# 4_STM32KIT_MCU.net
KiCad netlist of a schematic drawn in Altium Designer
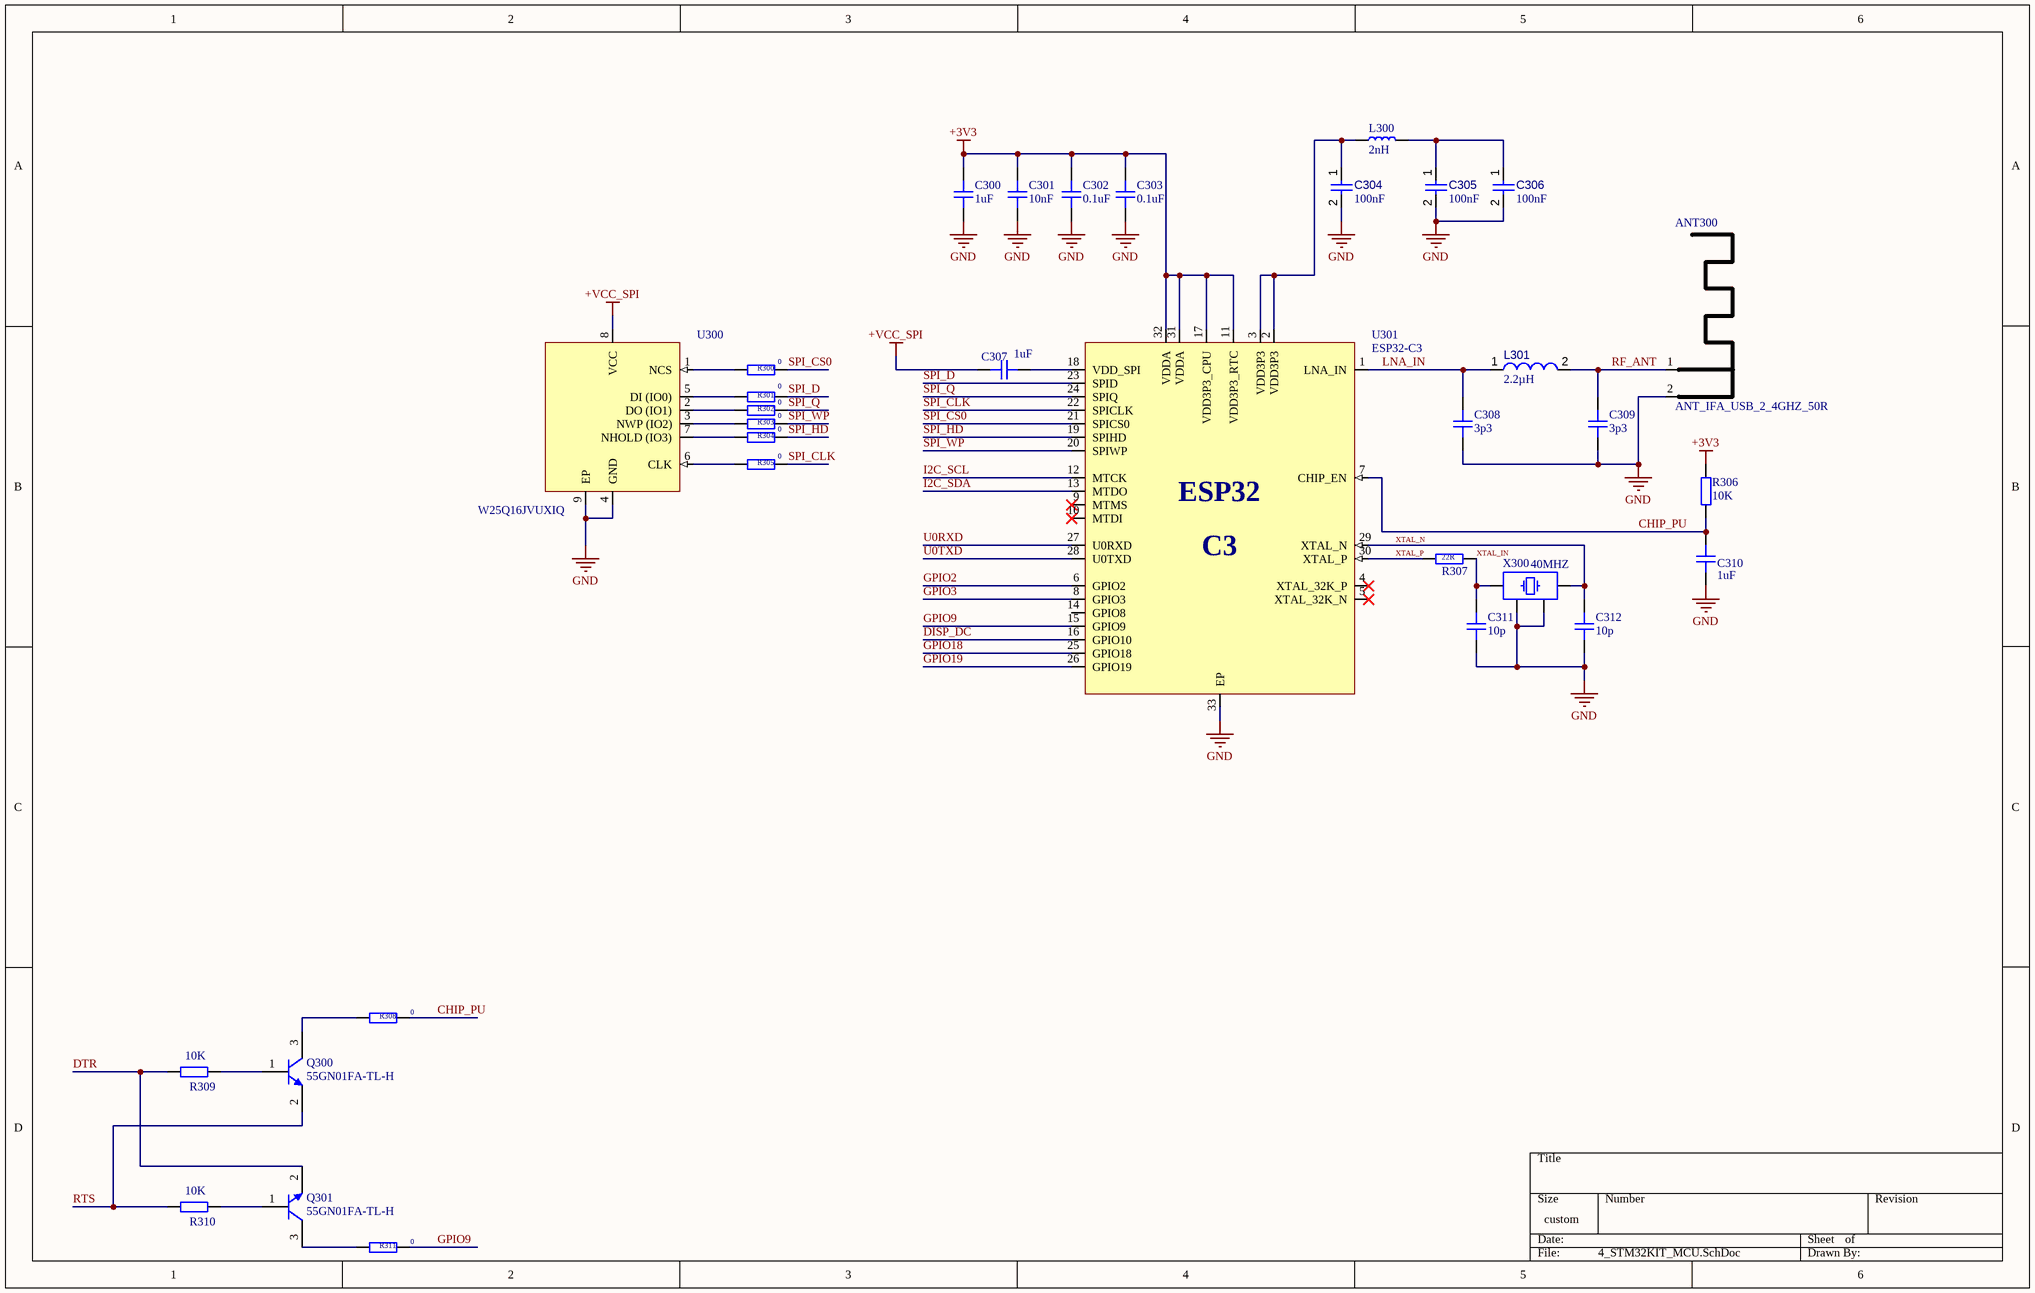
[diagram p0: 4_STM32KIT_MCU.SchDoc]

(export (version "E")
  (design (tool "Eeschema 10.0.6"))
  (components
    (comp (ref "ANT300")
      (value "ANT_IFA_USB_2_4GHZ_50R")
      (footprint "ANT_IFA_USB_2_4GHZ_50R")
      (description "Inverted F 2.4GHz ISM PCB Antenna 50 Ohm")
      (fields (field (name "SOURCE") "Schematic-Lib-PhilsLab.SchLib"))
      (libsource (lib "Industrial University of Ho Chi Minh City") (part "ANT_IFA_USB_2_4GHZ_50R"))
    )
    (comp (ref "C300")
      (value "1uF")
      (footprint "CAP_0402")
      (description "Capacitor SMD 0402 50V")
      (fields
        (field (name "MANUFACTURER") "Samsung")
        (field (name "MANUFACTURER PART NUMBER") "CL05B104KO5NNNC")
      )
      (libsource (lib "Schematic-Lib-PhilsLab") (part "CAP_0402_50V"))
    )
    (comp (ref "C301")
      (value "10nF")
      (footprint "CAP_0402")
      (description "Capacitor SMD 0402 50V")
      (fields
        (field (name "MANUFACTURER") "Samsung")
        (field (name "MANUFACTURER PART NUMBER") "CL05B104KO5NNNC")
      )
      (libsource (lib "Schematic-Lib-PhilsLab") (part "CAP_0402_50V"))
    )
    (comp (ref "C302")
      (value "0.1uF")
      (footprint "CAP_0402")
      (description "Capacitor SMD 0402 50V")
      (fields
        (field (name "MANUFACTURER") "Samsung")
        (field (name "MANUFACTURER PART NUMBER") "CL05B104KO5NNNC")
      )
      (libsource (lib "Schematic-Lib-PhilsLab") (part "CAP_0402_50V"))
    )
    (comp (ref "C303")
      (value "0.1uF")
      (footprint "CAP_0402")
      (description "Capacitor SMD 0402 50V")
      (fields
        (field (name "MANUFACTURER") "Samsung")
        (field (name "MANUFACTURER PART NUMBER") "CL05B104KO5NNNC")
      )
      (libsource (lib "Schematic-Lib-PhilsLab") (part "CAP_0402_50V"))
    )
    (comp (ref "C304")
      (value "100nF")
      (footprint "CAPC1005X56X25LL10T15")
      (description "Chip Capacitor, 0.1 uF, +/- 5%, 16 V, 0402 (1005 Metric)")
      (fields (field (name "TOLERANCE") "5%") (field (name "Comment") "Capacitor 0.1 uF +/- 5% 16 V 0402"))
      (libsource (lib "Industrial University of Ho Chi Minh City") (part "CAP-NP-2"))
    )
    (comp (ref "C305")
      (value "100nF")
      (footprint "CAPC1005X56X25LL10T15")
      (description "Chip Capacitor, 0.1 uF, +/- 5%, 16 V, 0402 (1005 Metric)")
      (fields (field (name "TOLERANCE") "5%") (field (name "Comment") "Capacitor 0.1 uF +/- 5% 16 V 0402"))
      (libsource (lib "Industrial University of Ho Chi Minh City") (part "CAP-NP-2"))
    )
    (comp (ref "C306")
      (value "100nF")
      (footprint "CAPC1005X56X25LL10T15")
      (description "Chip Capacitor, 0.1 uF, +/- 5%, 16 V, 0402 (1005 Metric)")
      (fields (field (name "TOLERANCE") "5%") (field (name "Comment") "10u"))
      (libsource (lib "Industrial University of Ho Chi Minh City") (part "CAP-NP-2"))
    )
    (comp (ref "C307")
      (value "1uF")
      (footprint "CAP_0402")
      (description "Capacitor SMD 0402")
      (fields (field (name "SOURCE") "Schematic-Lib-PhilsLab.SchLib"))
      (libsource (lib "Industrial University of Ho Chi Minh City") (part "CAP_EL_NP_5MM"))
    )
    (comp (ref "C308")
      (value "3p3")
      (footprint "CAP_0402")
      (description "Capacitor SMD 0402")
      (libsource (lib "Schematic-Lib-PhilsLab") (part "CAP_0402"))
    )
    (comp (ref "C309")
      (value "3p3")
      (footprint "CAP_0402")
      (description "Capacitor SMD 0402")
      (libsource (lib "Schematic-Lib-PhilsLab") (part "CAP_0402"))
    )
    (comp (ref "C310")
      (value "1uF")
      (footprint "CAP_0402")
      (description "Capacitor SMD 0402")
      (fields (field (name "SOURCE") "Schematic-Lib-PhilsLab.SchLib"))
      (libsource (lib "Industrial University of Ho Chi Minh City") (part "CAP_EL_NP_5MM"))
    )
    (comp (ref "C311")
      (value "10p")
      (footprint "CAP_0402")
      (description "Capacitor SMD 0402")
      (libsource (lib "Schematic-Lib-PhilsLab") (part "CAP_0402"))
    )
    (comp (ref "C312")
      (value "10p")
      (footprint "CAP_0402")
      (description "Capacitor SMD 0402")
      (libsource (lib "Schematic-Lib-PhilsLab") (part "CAP_0402"))
    )
    (comp (ref "L300")
      (value "2nH")
      (footprint "IND_0402")
      (description "Inductor SMD 0402")
      (libsource (lib "Schematic-Lib-PhilsLab") (part "IND_0402"))
    )
    (comp (ref "L301")
      (value "2.2µH")
      (footprint "IND1005X55X20VL5T10")
      (description "Chip Inductor, 2.2 nH, +/- 0.3 nH, 400 mA, -40 to 85 degC, 0402 (1005 Metric), RoHS, Tape and Reel")
      (fields (field (name "MANUFACTURER") "Panasonic") (field (name "TOLERANCE") "5%"))
      (libsource (lib "Industrial University of Ho Chi Minh City") (part "IND-2"))
    )
    (comp (ref "Q300")
      (value "55GN01FA-TL-H")
      (footprint "ONSC-SSFP-3_V")
      (description "RF Transistor, 10 V, 70 mA, fT=5.5 GHz, NPN Single, 3-Pin SSFP, Pb-Free, Tape and Reel")
      (fields (field (name "MANUFACTURER") "On Semiconductor"))
      (libsource (lib "Altium Content Vault") (part "ONSC-NPN-B1E2C3-3"))
    )
    (comp (ref "Q301")
      (value "55GN01FA-TL-H")
      (footprint "ONSC-SSFP-3_V")
      (description "RF Transistor, 10 V, 70 mA, fT=5.5 GHz, NPN Single, 3-Pin SSFP, Pb-Free, Tape and Reel")
      (fields (field (name "MANUFACTURER") "On Semiconductor"))
      (libsource (lib "Altium Content Vault") (part "ONSC-NPN-B1E2C3-3"))
    )
    (comp (ref "R300")
      (value "0")
      (footprint "RES_0402")
      (description "Resistor SMD 0402")
      (fields (field (name "SOURCE") "Schematic-Lib-PhilsLab.SchLib"))
      (libsource (lib "Industrial University of Ho Chi Minh City") (part "RES_5931"))
    )
    (comp (ref "R301")
      (value "0")
      (footprint "RES_0402")
      (description "Resistor SMD 0402")
      (fields (field (name "SOURCE") "Schematic-Lib-PhilsLab.SchLib"))
      (libsource (lib "Industrial University of Ho Chi Minh City") (part "RES_5931"))
    )
    (comp (ref "R302")
      (value "0")
      (footprint "RES_0402")
      (description "Resistor SMD 0402")
      (fields (field (name "SOURCE") "Schematic-Lib-PhilsLab.SchLib"))
      (libsource (lib "Industrial University of Ho Chi Minh City") (part "RES_5931"))
    )
    (comp (ref "R303")
      (value "0")
      (footprint "RES_0402")
      (description "Resistor SMD 0402")
      (fields (field (name "SOURCE") "Schematic-Lib-PhilsLab.SchLib"))
      (libsource (lib "Industrial University of Ho Chi Minh City") (part "RES_5931"))
    )
    (comp (ref "R304")
      (value "0")
      (footprint "RES_0402")
      (description "Resistor SMD 0402")
      (fields (field (name "SOURCE") "Schematic-Lib-PhilsLab.SchLib"))
      (libsource (lib "Industrial University of Ho Chi Minh City") (part "RES_5931"))
    )
    (comp (ref "R305")
      (value "0")
      (footprint "RES_0402")
      (description "Resistor SMD 0402")
      (fields (field (name "SOURCE") "Schematic-Lib-PhilsLab.SchLib"))
      (libsource (lib "Industrial University of Ho Chi Minh City") (part "RES_5931"))
    )
    (comp (ref "R306")
      (value "10K")
      (footprint "RES_0402")
      (description "Resistor SMD 0402")
      (fields (field (name "SOURCE") "Schematic-Lib-PhilsLab.SchLib"))
      (libsource (lib "Industrial University of Ho Chi Minh City") (part "RES_5931"))
    )
    (comp (ref "R307")
      (value "22R")
      (footprint "RES_0402")
      (description "Resistor SMD 0402")
      (fields (field (name "SOURCE") "Schematic-Lib-PhilsLab.SchLib"))
      (libsource (lib "Industrial University of Ho Chi Minh City") (part "RES_5931"))
    )
    (comp (ref "R308")
      (value "0")
      (footprint "RES_0402")
      (description "Resistor SMD 0402")
      (fields (field (name "SOURCE") "Schematic-Lib-PhilsLab.SchLib"))
      (libsource (lib "Industrial University of Ho Chi Minh City") (part "RES_5931"))
    )
    (comp (ref "R309")
      (value "10K")
      (footprint "RES_0402")
      (description "Resistor SMD 0402")
      (fields (field (name "SOURCE") "Schematic-Lib-PhilsLab.SchLib"))
      (libsource (lib "Industrial University of Ho Chi Minh City") (part "RES_5931"))
    )
    (comp (ref "R310")
      (value "10K")
      (footprint "RES_0402")
      (description "Resistor SMD 0402")
      (fields (field (name "SOURCE") "Schematic-Lib-PhilsLab.SchLib"))
      (libsource (lib "Industrial University of Ho Chi Minh City") (part "RES_5931"))
    )
    (comp (ref "R311")
      (value "0")
      (footprint "RES_0402")
      (description "Resistor SMD 0402")
      (fields (field (name "SOURCE") "Schematic-Lib-PhilsLab.SchLib"))
      (libsource (lib "Industrial University of Ho Chi Minh City") (part "RES_5931"))
    )
    (comp (ref "U300")
      (value "W25Q16JVUXIQ")
      (footprint "USON-8-2X3MM")
      (description "16M-BIT SERIAL FLASH MEMORY WITH DUAL/QUAD SPI USON-8")
      (fields (field (name "MANUFACTURER") "Winbond") (field (name "SOURCE") "Schematic-Lib-PhilsLab.SchLib"))
      (libsource (lib "Industrial University of Ho Chi Minh City") (part "W25Q16JVUXIQ"))
    )
    (comp (ref "U301")
      (value "ESP32-C3")
      (footprint "QFN32-5X5")
      (fields
        (field (name "MANUFACTURER") "Espressif")
        (field (name "SOURCE") "Schematic-Lib-PhilsLab.SchLib")
      )
      (libsource (lib "Industrial University of Ho Chi Minh City") (part "ESP32-C3"))
    )
    (comp (ref "X300")
      (value "40MHZ")
      (footprint "XTAL_2520")
      (description "Crystal SMD 2520")
      (libsource (lib "Schematic-Lib-PhilsLab") (part "XTAL_2520"))
    )
  )
  (nets
    (net (code "1") (name "+3V3") (class "Default")
      (node (ref "C300") (pin "2") (pinfunction "2_2") (pintype "passive"))
      (node (ref "C301") (pin "2") (pinfunction "2_2") (pintype "passive"))
      (node (ref "C302") (pin "2") (pinfunction "2_2") (pintype "passive"))
      (node (ref "C303") (pin "2") (pinfunction "2_2") (pintype "passive"))
      (node (ref "R306") (pin "2") (pinfunction "2_2") (pintype "passive"))
      (node (ref "U301") (pin "11") (pinfunction "VDD3P3_RTC_11") (pintype "power_in"))
      (node (ref "U301") (pin "17") (pinfunction "VDD3P3_CPU_17") (pintype "power_in"))
      (node (ref "U301") (pin "31") (pinfunction "VDDA_31") (pintype "power_in"))
      (node (ref "U301") (pin "32") (pinfunction "VDDA_32") (pintype "power_in"))
    )
    (net (code "2") (name "+VCC_SPI") (class "Default")
      (node (ref "C307") (pin "1") (pinfunction "1_1") (pintype "passive"))
      (node (ref "U300") (pin "8") (pinfunction "VCC_8") (pintype "power_in"))
    )
    (net (code "3") (name "/CHIP_PU") (class "Default")
      (node (ref "C310") (pin "2") (pinfunction "2_2") (pintype "passive"))
      (node (ref "R306") (pin "1") (pinfunction "1_1") (pintype "passive"))
      (node (ref "R308") (pin "2") (pinfunction "2_2") (pintype "passive"))
      (node (ref "U301") (pin "7") (pinfunction "CHIP_EN_7") (pintype "input"))
    )
    (net (code "4") (name "/DISP_DC") (class "Default")
      (node (ref "U301") (pin "16") (pinfunction "GPIO10_16") (pintype "bidirectional"))
    )
    (net (code "5") (name "/DTR") (class "Default")
      (node (ref "Q301") (pin "2") (pinfunction "E_2") (pintype "passive"))
      (node (ref "R309") (pin "1") (pinfunction "1_1") (pintype "passive"))
    )
    (net (code "6") (name "/GPIO2") (class "Default")
      (node (ref "U301") (pin "6") (pinfunction "GPIO2_6") (pintype "bidirectional"))
    )
    (net (code "7") (name "/GPIO3") (class "Default")
      (node (ref "U301") (pin "8") (pinfunction "GPIO3_8") (pintype "bidirectional"))
    )
    (net (code "8") (name "/GPIO9") (class "Default")
      (node (ref "R311") (pin "2") (pinfunction "2_2") (pintype "passive"))
      (node (ref "U301") (pin "15") (pinfunction "GPIO9_15") (pintype "bidirectional"))
    )
    (net (code "9") (name "/GPIO18") (class "Default")
      (node (ref "U301") (pin "25") (pinfunction "GPIO18_25") (pintype "bidirectional"))
    )
    (net (code "10") (name "/GPIO19") (class "Default")
      (node (ref "U301") (pin "26") (pinfunction "GPIO19_26") (pintype "bidirectional"))
    )
    (net (code "11") (name "/I2C_SCL") (class "Default")
      (node (ref "U301") (pin "12") (pinfunction "MTCK_12") (pintype "bidirectional"))
    )
    (net (code "12") (name "/I2C_SDA") (class "Default")
      (node (ref "U301") (pin "13") (pinfunction "MTDO_13") (pintype "bidirectional"))
    )
    (net (code "13") (name "/LNA_IN") (class "Default")
      (node (ref "C308") (pin "2") (pinfunction "2_2") (pintype "passive"))
      (node (ref "L301") (pin "1") (pinfunction "1_1") (pintype "passive"))
      (node (ref "U301") (pin "1") (pinfunction "LNA_IN_1") (pintype "bidirectional"))
    )
    (net (code "14") (name "/RF_ANT") (class "Default")
      (node (ref "ANT300") (pin "1") (pinfunction "RF_1") (pintype "passive"))
      (node (ref "C309") (pin "2") (pinfunction "2_2") (pintype "passive"))
      (node (ref "L301") (pin "2") (pinfunction "2_2") (pintype "passive"))
    )
    (net (code "15") (name "/RTS") (class "Default")
      (node (ref "Q300") (pin "2") (pinfunction "E_2") (pintype "passive"))
      (node (ref "R310") (pin "1") (pinfunction "1_1") (pintype "passive"))
    )
    (net (code "16") (name "/SPI_CLK") (class "Default")
      (node (ref "R305") (pin "2") (pinfunction "2_2") (pintype "passive"))
      (node (ref "U301") (pin "22") (pinfunction "SPICLK_22") (pintype "bidirectional"))
    )
    (net (code "17") (name "/SPI_CS0") (class "Default")
      (node (ref "R300") (pin "2") (pinfunction "2_2") (pintype "passive"))
      (node (ref "U301") (pin "21") (pinfunction "SPICS0_21") (pintype "bidirectional"))
    )
    (net (code "18") (name "/SPI_D") (class "Default")
      (node (ref "R301") (pin "2") (pinfunction "2_2") (pintype "passive"))
      (node (ref "U301") (pin "23") (pinfunction "SPID_23") (pintype "bidirectional"))
    )
    (net (code "19") (name "/SPI_HD") (class "Default")
      (node (ref "R304") (pin "2") (pinfunction "2_2") (pintype "passive"))
      (node (ref "U301") (pin "19") (pinfunction "SPIHD_19") (pintype "bidirectional"))
    )
    (net (code "20") (name "/SPI_Q") (class "Default")
      (node (ref "R302") (pin "2") (pinfunction "2_2") (pintype "passive"))
      (node (ref "U301") (pin "24") (pinfunction "SPIQ_24") (pintype "bidirectional"))
    )
    (net (code "21") (name "/SPI_WP") (class "Default")
      (node (ref "R303") (pin "2") (pinfunction "2_2") (pintype "passive"))
      (node (ref "U301") (pin "20") (pinfunction "SPIWP_20") (pintype "bidirectional"))
    )
    (net (code "22") (name "/U0RXD") (class "Default")
      (node (ref "U301") (pin "27") (pinfunction "U0RXD_27") (pintype "bidirectional"))
    )
    (net (code "23") (name "/U0TXD") (class "Default")
      (node (ref "U301") (pin "28") (pinfunction "U0TXD_28") (pintype "bidirectional"))
    )
    (net (code "24") (name "/XTAL_IN") (class "Default")
      (node (ref "C311") (pin "2") (pinfunction "2_2") (pintype "passive"))
      (node (ref "R307") (pin "2") (pinfunction "2_2") (pintype "passive"))
      (node (ref "X300") (pin "1") (pinfunction "1_1") (pintype "passive"))
    )
    (net (code "25") (name "/XTAL_N") (class "Default")
      (node (ref "C312") (pin "2") (pinfunction "2_2") (pintype "passive"))
      (node (ref "U301") (pin "29") (pinfunction "XTAL_N_29") (pintype "input"))
      (node (ref "X300") (pin "3") (pinfunction "3_3") (pintype "passive"))
    )
    (net (code "26") (name "/XTAL_P") (class "Default")
      (node (ref "R307") (pin "1") (pinfunction "1_1") (pintype "passive"))
      (node (ref "U301") (pin "30") (pinfunction "XTAL_P_30") (pintype "input"))
    )
    (net (code "27") (name "GND") (class "Default")
      (node (ref "ANT300") (pin "2") (pinfunction "GND_2") (pintype "passive"))
      (node (ref "C300") (pin "1") (pinfunction "1_1") (pintype "passive"))
      (node (ref "C301") (pin "1") (pinfunction "1_1") (pintype "passive"))
      (node (ref "C302") (pin "1") (pinfunction "1_1") (pintype "passive"))
      (node (ref "C303") (pin "1") (pinfunction "1_1") (pintype "passive"))
      (node (ref "C304") (pin "2") (pinfunction "2_2") (pintype "passive"))
      (node (ref "C305") (pin "2") (pinfunction "2_2") (pintype "passive"))
      (node (ref "C306") (pin "2") (pinfunction "2_2") (pintype "passive"))
      (node (ref "C308") (pin "1") (pinfunction "1_1") (pintype "passive"))
      (node (ref "C309") (pin "1") (pinfunction "1_1") (pintype "passive"))
      (node (ref "C310") (pin "1") (pinfunction "1_1") (pintype "passive"))
      (node (ref "C311") (pin "1") (pinfunction "1_1") (pintype "passive"))
      (node (ref "C312") (pin "1") (pinfunction "1_1") (pintype "passive"))
      (node (ref "U300") (pin "4") (pinfunction "GND_4") (pintype "power_in"))
      (node (ref "U300") (pin "9") (pinfunction "EP_9") (pintype "power_in"))
      (node (ref "U301") (pin "33") (pinfunction "EP_33") (pintype "power_in"))
      (node (ref "X300") (pin "2") (pinfunction "2_2") (pintype "passive"))
      (node (ref "X300") (pin "4") (pinfunction "4_4") (pintype "passive"))
    )
    (net (code "28") (name "Net-(C304-Pad1)") (class "Default")
      (node (ref "C304") (pin "1") (pinfunction "1_1") (pintype "passive"))
      (node (ref "L300") (pin "1") (pinfunction "1_1") (pintype "passive"))
      (node (ref "U301") (pin "2") (pinfunction "VDD3P3_2") (pintype "power_in"))
      (node (ref "U301") (pin "3") (pinfunction "VDD3P3_3") (pintype "power_in"))
    )
    (net (code "29") (name "Net-(C305-Pad1)") (class "Default")
      (node (ref "C305") (pin "1") (pinfunction "1_1") (pintype "passive"))
      (node (ref "C306") (pin "1") (pinfunction "1_1") (pintype "passive"))
      (node (ref "L300") (pin "2") (pinfunction "2_2") (pintype "passive"))
    )
    (net (code "30") (name "Net-(Q300-B)") (class "Default")
      (node (ref "Q300") (pin "1") (pinfunction "B_1") (pintype "passive"))
      (node (ref "R309") (pin "2") (pinfunction "2_2") (pintype "passive"))
    )
    (net (code "31") (name "Net-(Q300-C)") (class "Default")
      (node (ref "Q300") (pin "3") (pinfunction "C_3") (pintype "passive"))
      (node (ref "R308") (pin "1") (pinfunction "1_1") (pintype "passive"))
    )
    (net (code "32") (name "Net-(Q301-B)") (class "Default")
      (node (ref "Q301") (pin "1") (pinfunction "B_1") (pintype "passive"))
      (node (ref "R310") (pin "2") (pinfunction "2_2") (pintype "passive"))
    )
    (net (code "33") (name "Net-(Q301-C)") (class "Default")
      (node (ref "Q301") (pin "3") (pinfunction "C_3") (pintype "passive"))
      (node (ref "R311") (pin "1") (pinfunction "1_1") (pintype "passive"))
    )
    (net (code "34") (name "Net-(U300-CLK)") (class "Default")
      (node (ref "R305") (pin "1") (pinfunction "1_1") (pintype "passive"))
      (node (ref "U300") (pin "6") (pinfunction "CLK_6") (pintype "input"))
    )
    (net (code "35") (name "Net-(U300-DI_(IO0))") (class "Default")
      (node (ref "R301") (pin "1") (pinfunction "1_1") (pintype "passive"))
      (node (ref "U300") (pin "5") (pinfunction "DI_(IO0)_5") (pintype "bidirectional"))
    )
    (net (code "36") (name "Net-(U300-DO_(IO1))") (class "Default")
      (node (ref "R302") (pin "1") (pinfunction "1_1") (pintype "passive"))
      (node (ref "U300") (pin "2") (pinfunction "DO_(IO1)_2") (pintype "bidirectional"))
    )
    (net (code "37") (name "Net-(U300-NCS)") (class "Default")
      (node (ref "R300") (pin "1") (pinfunction "1_1") (pintype "passive"))
      (node (ref "U300") (pin "1") (pinfunction "NCS_1") (pintype "input"))
    )
    (net (code "38") (name "Net-(U300-NHOLD_(IO3))") (class "Default")
      (node (ref "R304") (pin "1") (pinfunction "1_1") (pintype "passive"))
      (node (ref "U300") (pin "7") (pinfunction "NHOLD_(IO3)_7") (pintype "bidirectional"))
    )
    (net (code "39") (name "Net-(U300-NWP_(IO2))") (class "Default")
      (node (ref "R303") (pin "1") (pinfunction "1_1") (pintype "passive"))
      (node (ref "U300") (pin "3") (pinfunction "NWP_(IO2)_3") (pintype "bidirectional"))
    )
    (net (code "40") (name "Net-(U301-VDD_SPI)") (class "Default")
      (node (ref "C307") (pin "2") (pinfunction "2_2") (pintype "passive"))
      (node (ref "U301") (pin "18") (pinfunction "VDD_SPI_18") (pintype "power_in"))
    )
    (net (code "41") (name "unconnected-(U301-GPIO8-Pad14)") (class "Default")
      (node (ref "U301") (pin "14") (pinfunction "GPIO8_14") (pintype "bidirectional"))
    )
    (net (code "42") (name "unconnected-(U301-MTDI-Pad10)") (class "Default")
      (node (ref "U301") (pin "10") (pinfunction "MTDI_10") (pintype "bidirectional+no_connect"))
    )
    (net (code "43") (name "unconnected-(U301-MTMS-Pad9)") (class "Default")
      (node (ref "U301") (pin "9") (pinfunction "MTMS_9") (pintype "bidirectional+no_connect"))
    )
    (net (code "44") (name "unconnected-(U301-XTAL_32K_N-Pad5)") (class "Default")
      (node (ref "U301") (pin "5") (pinfunction "XTAL_32K_N_5") (pintype "bidirectional+no_connect"))
    )
    (net (code "45") (name "unconnected-(U301-XTAL_32K_P-Pad4)") (class "Default")
      (node (ref "U301") (pin "4") (pinfunction "XTAL_32K_P_4") (pintype "bidirectional+no_connect"))
    )
  )
)
